# EDF.net
KiCad netlist of a schematic drawn in Altium Designer
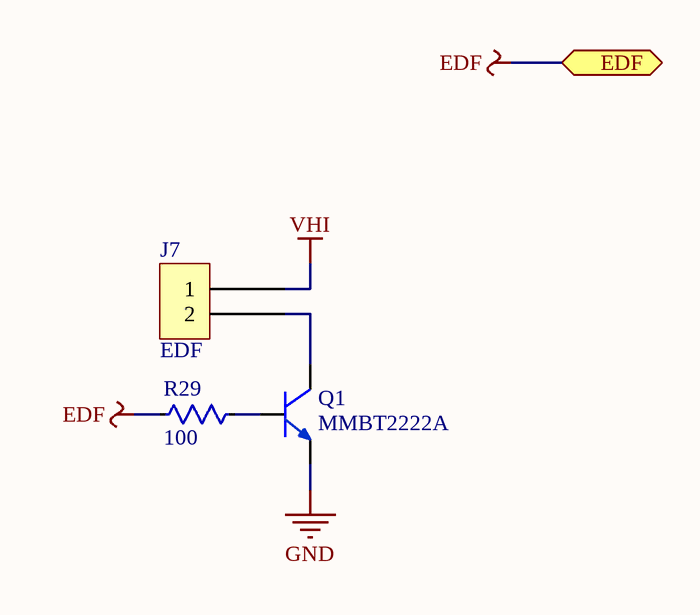
[diagram p0: EDF.SchDoc]

(export (version "E")
  (design (tool "Eeschema 10.0.6"))
  (components
    (comp (ref "J7")
      (value "EDF")
      (footprint "HEADER 1x2")
      (libsource (lib "AltiumLibrary") (part "Header 1x2"))
    )
    (comp (ref "Q1") (value "MMBT2222A") (footprint "SOT-23") (libsource (lib "AltiumLibrary") (part "NPN")))
    (comp (ref "R29")
      (value "100")
      (footprint "R1206")
      (fields (field (name "Comment") "RES"))
      (libsource (lib "AltiumLibrary") (part "RES"))
    )
  )
  (nets
    (net (code "1") (name "EDF") (class "Default") (node (ref "R29") (pin "1") (pintype "passive")))
    (net (code "2") (name "GND") (class "Default")
      (node (ref "Q1") (pin "E") (pinfunction "E_E") (pintype "passive"))
    )
    (net (code "3") (name "Net-(J7-Pad2)") (class "Default")
      (node (ref "J7") (pin "2") (pinfunction "2_2") (pintype "passive"))
      (node (ref "Q1") (pin "C") (pinfunction "C_C") (pintype "passive"))
    )
    (net (code "4") (name "Net-(Q1-PadB)") (class "Default")
      (node (ref "Q1") (pin "B") (pinfunction "B_B") (pintype "passive"))
      (node (ref "R29") (pin "2") (pintype "passive"))
    )
    (net (code "5") (name "VHI") (class "Default")
      (node (ref "J7") (pin "1") (pinfunction "1_1") (pintype "passive"))
    )
  )
)
